# FinalDesignCurrentMirror.net
KiCad netlist of a schematic drawn in Altium Designer
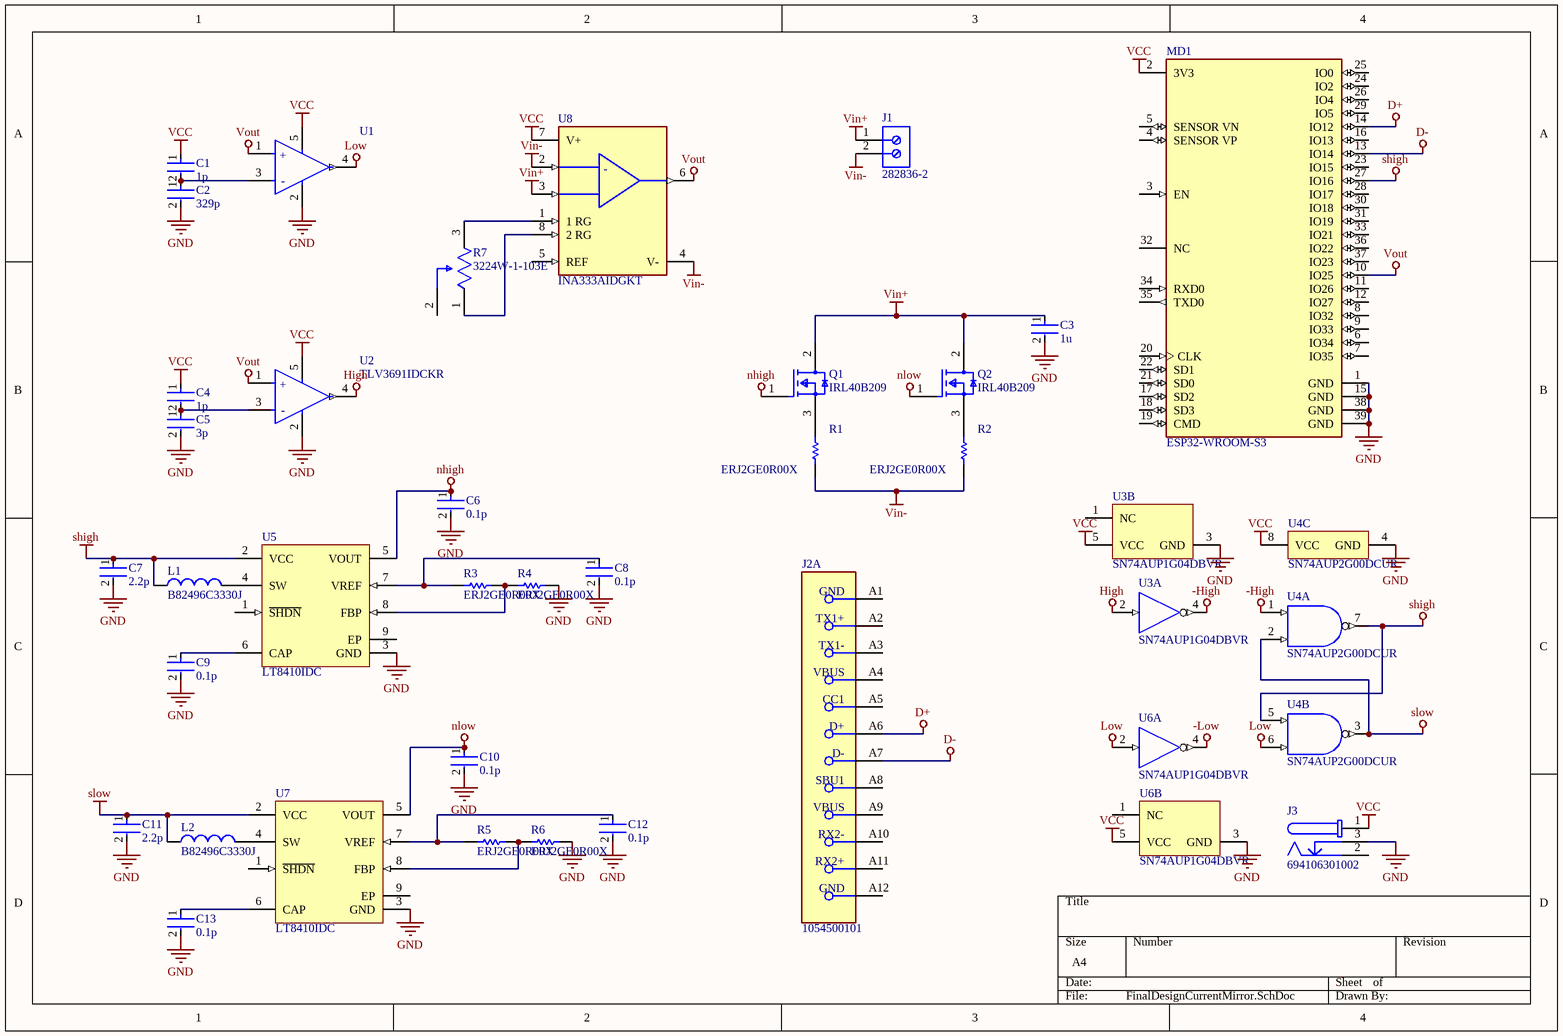
[diagram p0: FinalDesignCurrentMirror.SchDoc]

(export (version "E")
  (design (tool "Eeschema 10.0.6"))
  (components
    (comp (ref "C1")
      (value "1p")
      (footprint "FP-GRM188-0_1-e0_2_0_55-IPC_A")
      (description "Chip Multilayer Ceramic Capacitors for General Purpose, 0603, 10uF, X5R, 15%, 20%, 6.3V")
      (fields (field (name "VOLTAGE") "6.3V") (field (name "TOLERANCE") "20%"))
      (libsource (lib "Altium Content Vault") (part "02cd4be3c70576c341d710602a673aa"))
    )
    (comp (ref "C2")
      (value "329p")
      (footprint "FP-GRM188-0_1-e0_2_0_55-IPC_A")
      (description "Chip Multilayer Ceramic Capacitors for General Purpose, 0603, 10uF, X5R, 15%, 20%, 6.3V")
      (fields (field (name "VOLTAGE") "6.3V") (field (name "TOLERANCE") "20%"))
      (libsource (lib "Altium Content Vault") (part "02cd4be3c70576c341d710602a673aa"))
    )
    (comp (ref "C3")
      (value "1u")
      (footprint "FP-GRM188-0_1-e0_2_0_55-IPC_A")
      (description "Chip Multilayer Ceramic Capacitors for General Purpose, 0603, 10uF, X5R, 15%, 20%, 6.3V")
      (fields (field (name "VOLTAGE") "6.3V") (field (name "TOLERANCE") "20%"))
      (libsource (lib "Altium Content Vault") (part "02cd4be3c70576c341d710602a673aa"))
    )
    (comp (ref "C4")
      (value "1p")
      (footprint "FP-GRM188-0_1-e0_2_0_55-IPC_A")
      (description "Chip Multilayer Ceramic Capacitors for General Purpose, 0603, 10uF, X5R, 15%, 20%, 6.3V")
      (fields (field (name "VOLTAGE") "6.3V") (field (name "TOLERANCE") "20%"))
      (libsource (lib "Altium Content Vault") (part "02cd4be3c70576c341d710602a673aa"))
    )
    (comp (ref "C5")
      (value "3p")
      (footprint "FP-GRM188-0_1-e0_2_0_55-IPC_A")
      (description "Chip Multilayer Ceramic Capacitors for General Purpose, 0603, 10uF, X5R, 15%, 20%, 6.3V")
      (fields (field (name "VOLTAGE") "6.3V") (field (name "TOLERANCE") "20%"))
      (libsource (lib "Altium Content Vault") (part "02cd4be3c70576c341d710602a673aa"))
    )
    (comp (ref "C6")
      (value "0.1p")
      (footprint "FP-GRM188-0_1-e0_2_0_55-IPC_A")
      (description "Chip Multilayer Ceramic Capacitors for General Purpose, 0603, 10uF, X5R, 15%, 20%, 6.3V")
      (fields (field (name "VOLTAGE") "6.3V") (field (name "TOLERANCE") "20%"))
      (libsource (lib "Altium Content Vault") (part "02cd4be3c70576c341d710602a673aa"))
    )
    (comp (ref "C7")
      (value "2.2p")
      (footprint "FP-GRM188-0_1-e0_2_0_55-IPC_A")
      (description "Chip Multilayer Ceramic Capacitors for General Purpose, 0603, 10uF, X5R, 15%, 20%, 6.3V")
      (fields (field (name "VOLTAGE") "6.3V") (field (name "TOLERANCE") "20%"))
      (libsource (lib "Altium Content Vault") (part "02cd4be3c70576c341d710602a673aa"))
    )
    (comp (ref "C8")
      (value "0.1p")
      (footprint "FP-GRM188-0_1-e0_2_0_55-IPC_A")
      (description "Chip Multilayer Ceramic Capacitors for General Purpose, 0603, 10uF, X5R, 15%, 20%, 6.3V")
      (fields (field (name "VOLTAGE") "6.3V") (field (name "TOLERANCE") "20%"))
      (libsource (lib "Altium Content Vault") (part "02cd4be3c70576c341d710602a673aa"))
    )
    (comp (ref "C9")
      (value "0.1p")
      (footprint "FP-GRM188-0_1-e0_2_0_55-IPC_A")
      (description "Chip Multilayer Ceramic Capacitors for General Purpose, 0603, 10uF, X5R, 15%, 20%, 6.3V")
      (fields (field (name "VOLTAGE") "6.3V") (field (name "TOLERANCE") "20%"))
      (libsource (lib "Altium Content Vault") (part "02cd4be3c70576c341d710602a673aa"))
    )
    (comp (ref "C10")
      (value "0.1p")
      (footprint "FP-GRM188-0_1-e0_2_0_55-IPC_A")
      (description "Chip Multilayer Ceramic Capacitors for General Purpose, 0603, 10uF, X5R, 15%, 20%, 6.3V")
      (fields (field (name "VOLTAGE") "6.3V") (field (name "TOLERANCE") "20%"))
      (libsource (lib "Altium Content Vault") (part "02cd4be3c70576c341d710602a673aa"))
    )
    (comp (ref "C11")
      (value "2.2p")
      (footprint "FP-GRM188-0_1-e0_2_0_55-IPC_A")
      (description "Chip Multilayer Ceramic Capacitors for General Purpose, 0603, 10uF, X5R, 15%, 20%, 6.3V")
      (fields (field (name "VOLTAGE") "6.3V") (field (name "TOLERANCE") "20%"))
      (libsource (lib "Altium Content Vault") (part "02cd4be3c70576c341d710602a673aa"))
    )
    (comp (ref "C12")
      (value "0.1p")
      (footprint "FP-GRM188-0_1-e0_2_0_55-IPC_A")
      (description "Chip Multilayer Ceramic Capacitors for General Purpose, 0603, 10uF, X5R, 15%, 20%, 6.3V")
      (fields (field (name "VOLTAGE") "6.3V") (field (name "TOLERANCE") "20%"))
      (libsource (lib "Altium Content Vault") (part "02cd4be3c70576c341d710602a673aa"))
    )
    (comp (ref "C13")
      (value "0.1p")
      (footprint "FP-GRM188-0_1-e0_2_0_55-IPC_A")
      (description "Chip Multilayer Ceramic Capacitors for General Purpose, 0603, 10uF, X5R, 15%, 20%, 6.3V")
      (fields (field (name "VOLTAGE") "6.3V") (field (name "TOLERANCE") "20%"))
      (libsource (lib "Altium Content Vault") (part "02cd4be3c70576c341d710602a673aa"))
    )
    (comp (ref "J1")
      (value "282836-2")
      (footprint "TECO-282836-2_V")
      (description "Female Header, Pitch 5 mm, 1 x 2 Position, Height 10 mm, Tail Length 3.5 mm, Rohs, Bulk")
      (fields (field (name "VOLTAGE") "300V") (field (name "MANUFACTURER") "TE Connectivity"))
      (libsource (lib "Altium Content Vault") (part "CN-1P-F-TB2"))
    )
    (comp (ref "J2")
      (value "1054500101")
      (footprint "FP-1054500101-MFG")
      (description "USB Shielded I/O Receptacle; Type C; Right Angle; Surface Mount; Gold over Nickel")
      (fields (field (name "MANUFACTURER") "Molex"))
      (libsource (lib "Altium Content Vault") (part "9808b19ecaf079fb99eed69f0495cd0"))
    )
    (comp (ref "J3")
      (value "694106301002")
      (footprint "694106301002")
      (libsource (lib "Altium Content Vault") (part "DC Power Jack"))
    )
    (comp (ref "L1")
      (value "B82496C3330J")
      (footprint "INDC1608X90X30LL10T20")
      (fields (field (name "MANUFACTURER") "EPCOS-(TDK)") (field (name "TOLERANCE") "±5%"))
      (libsource (lib "Altium Content Vault") (part "IND-2"))
    )
    (comp (ref "L2")
      (value "B82496C3330J")
      (footprint "INDC1608X90X30LL10T20")
      (fields (field (name "MANUFACTURER") "EPCOS-(TDK)") (field (name "TOLERANCE") "±5%"))
      (libsource (lib "Altium Content Vault") (part "IND-2"))
    )
    (comp (ref "MD1")
      (value "ESP32-WROOM-S3")
      (footprint "FP-ESP32-WROOM-32D-MFG")
      (description "WIFI MODULE 32MBITS SPI FLASH")
      (fields
        (field (name "OCTOPART") "https://octopart.com/esp32-wroom-32d-espressif+systems-91040050")
        (field (name "MANUFACTURER") "Espressif Systems")
      )
      (libsource (lib "Altium Content Vault") (part "a031a76f8c27026a7a7f4657ff233a3"))
    )
    (comp (ref "Q1")
      (value "IRL40B209")
      (footprint "FP-PG-TO220-3-MFG")
      (description "MOSFET N-CH 40V 195A")
      (libsource (lib "Altium Content Vault") (part "277670f45256a45703965f138927d09"))
    )
    (comp (ref "Q2")
      (value "IRL40B209")
      (footprint "FP-PG-TO220-3-MFG")
      (description "MOSFET N-CH 40V 195A")
      (libsource (lib "Altium Content Vault") (part "277670f45256a45703965f138927d09"))
    )
    (comp (ref "R1")
      (value "ERJ2GE0R00X")
      (footprint "RESC1005X40X25LL05T05")
      (description "Chip Resistor, 0 Ohm, 0.1 W, -55 to 155 degC, 0402 (1005 Metric), RoHS, Tape and Reel")
      (fields (field (name "MANUFACTURER") "Panasonic") (field (name "TOLERANCE") "5%"))
      (libsource (lib "Altium Content Vault") (part "RES-2"))
    )
    (comp (ref "R2")
      (value "ERJ2GE0R00X")
      (footprint "RESC1005X40X25LL05T05")
      (description "Chip Resistor, 0 Ohm, 0.1 W, -55 to 155 degC, 0402 (1005 Metric), RoHS, Tape and Reel")
      (fields (field (name "MANUFACTURER") "Panasonic") (field (name "TOLERANCE") "5%"))
      (libsource (lib "Altium Content Vault") (part "RES-2"))
    )
    (comp (ref "R3")
      (value "ERJ2GE0R00X")
      (footprint "RESC1005X40X25LL05T05")
      (description "Chip Resistor, 0 Ohm, 0.1 W, -55 to 155 degC, 0402 (1005 Metric), RoHS, Tape and Reel")
      (fields (field (name "MANUFACTURER") "Panasonic") (field (name "TOLERANCE") "5%"))
      (libsource (lib "Altium Content Vault") (part "RES-2"))
    )
    (comp (ref "R4")
      (value "ERJ2GE0R00X")
      (footprint "RESC1005X40X25LL05T05")
      (description "Chip Resistor, 0 Ohm, 0.1 W, -55 to 155 degC, 0402 (1005 Metric), RoHS, Tape and Reel")
      (fields (field (name "MANUFACTURER") "Panasonic") (field (name "TOLERANCE") "5%"))
      (libsource (lib "Altium Content Vault") (part "RES-2"))
    )
    (comp (ref "R5")
      (value "ERJ2GE0R00X")
      (footprint "RESC1005X40X25LL05T05")
      (description "Chip Resistor, 0 Ohm, 0.1 W, -55 to 155 degC, 0402 (1005 Metric), RoHS, Tape and Reel")
      (fields (field (name "MANUFACTURER") "Panasonic") (field (name "TOLERANCE") "5%"))
      (libsource (lib "Altium Content Vault") (part "RES-2"))
    )
    (comp (ref "R6")
      (value "ERJ2GE0R00X")
      (footprint "RESC1005X40X25LL05T05")
      (description "Chip Resistor, 0 Ohm, 0.1 W, -55 to 155 degC, 0402 (1005 Metric), RoHS, Tape and Reel")
      (fields (field (name "MANUFACTURER") "Panasonic") (field (name "TOLERANCE") "5%"))
      (libsource (lib "Altium Content Vault") (part "RES-2"))
    )
    (comp (ref "R7")
      (value "3224W-1-103E")
      (footprint "FP-3224W-MFG")
      (description "TRIMMER 10K OHM 0.25W J LEAD TOP")
      (fields (field (name "TOLERANCE") "10%") (field (name "MANUFACTURER") "Bourns"))
      (libsource (lib "Altium Content Vault") (part "83d3d349ed884d1db45cec512f27eb6"))
    )
    (comp (ref "U1")
      (value "~")
      (footprint "FP-DCK0005A-IPC_A")
      (description "IC COMPARATOR NANO-POWER SC70-5")
      (libsource (lib "Altium Content Vault") (part "3dae5d43319efa9f60be5f7de20330d"))
    )
    (comp (ref "U2")
      (value "TLV3691IDCKR")
      (footprint "FP-DCK0005A-IPC_A")
      (description "IC COMPARATOR NANO-POWER SC70-5")
      (libsource (lib "Altium Content Vault") (part "3dae5d43319efa9f60be5f7de20330d"))
    )
    (comp (ref "U3")
      (value "SN74AUP1G04DBVR")
      (footprint "DBV0005A_L")
      (description "Low-Power Single Inverter Gate, DBV0005A, LARGE T&R")
      (fields
        (field (name "GENERIC PART NUMBER") "SN74AUP1G04")
        (field (name "MANUFACTURER") "Texas Instruments")
      )
      (libsource (lib "Altium Content Vault") (part "TI-SN74XXX1XX4-XX-5"))
    )
    (comp (ref "U4")
      (value "SN74AUP2G00DCUR")
      (footprint "DCU0008A_L")
      (description "Low-Power Dual 2-Input Positive-NAND Gate, DCU0008A, LARGE T&R")
      (fields
        (field (name "GENERIC PART NUMBER") "SN74AUP2G00")
        (field (name "MANUFACTURER") "Texas Instruments")
      )
      (libsource (lib "Altium Content Vault") (part "TI-SN74XXX2GXXX-8"))
    )
    (comp (ref "U5")
      (value "LT8410IDC")
      (footprint "LT-DC8_V")
      (fields
        (field (name "PARTNUMBER") "LT8410IDC-1#TRMPBF")
        (field (name "MANUFACTURER") "Linear Technology")
      )
      (libsource (lib "Altium Content Vault") (part "LT-LT8410-1_8410-DC8-8"))
    )
    (comp (ref "U6")
      (value "SN74AUP1G04DBVR")
      (footprint "DBV0005A_L")
      (description "Low-Power Single Inverter Gate, DBV0005A, LARGE T&R")
      (fields
        (field (name "GENERIC PART NUMBER") "SN74AUP1G04")
        (field (name "MANUFACTURER") "Texas Instruments")
      )
      (libsource (lib "Altium Content Vault") (part "TI-SN74XXX1XX4-XX-5"))
    )
    (comp (ref "U7")
      (value "LT8410IDC")
      (footprint "LT-DC8_V")
      (fields
        (field (name "PARTNUMBER") "LT8410IDC-1#TRMPBF")
        (field (name "MANUFACTURER") "Linear Technology")
      )
      (libsource (lib "Altium Content Vault") (part "LT-LT8410-1_8410-DC8-8"))
    )
    (comp (ref "U8")
      (value "INA333AIDGKT")
      (footprint "FP-DGK0008A-MFG")
      (description "Instrumentation Amplifier 1 Circuit Rail-to-Rail 8-VSSOP")
      (fields (field (name "MANUFACTURER") "Texas Instruments"))
      (libsource (lib "Altium Content Vault") (part "14c63953c288e0173d78c5cf827a12c"))
    )
  )
  (nets
    (net (code "1") (name "-High") (class "Default")
      (node (ref "U3") (pin "4") (pinfunction "Y_4") (pintype "output"))
      (node (ref "U4") (pin "1") (pinfunction "1A_1") (pintype "input"))
    )
    (net (code "2") (name "-Low") (class "Default")
      (node (ref "U6") (pin "4") (pinfunction "Y_4") (pintype "output"))
    )
    (net (code "3") (name "D+") (class "Default")
      (node (ref "J2") (pin "A6") (pinfunction "D+_A6") (pintype "passive"))
      (node (ref "MD1") (pin "14") (pinfunction "IO12_14") (pintype "bidirectional"))
    )
    (net (code "4") (name "D-") (class "Default")
      (node (ref "J2") (pin "A7") (pinfunction "D-_A7") (pintype "passive"))
      (node (ref "MD1") (pin "13") (pinfunction "IO14_13") (pintype "bidirectional"))
    )
    (net (code "5") (name "GND") (class "Default")
      (node (ref "C10") (pin "2") (pinfunction "2_2") (pintype "passive"))
      (node (ref "C11") (pin "2") (pinfunction "2_2") (pintype "passive"))
      (node (ref "C12") (pin "2") (pinfunction "2_2") (pintype "passive"))
      (node (ref "C13") (pin "2") (pinfunction "2_2") (pintype "passive"))
      (node (ref "C2") (pin "2") (pinfunction "2_2") (pintype "passive"))
      (node (ref "C3") (pin "2") (pinfunction "2_2") (pintype "passive"))
      (node (ref "C5") (pin "2") (pinfunction "2_2") (pintype "passive"))
      (node (ref "C6") (pin "2") (pinfunction "2_2") (pintype "passive"))
      (node (ref "C7") (pin "2") (pinfunction "2_2") (pintype "passive"))
      (node (ref "C8") (pin "2") (pinfunction "2_2") (pintype "passive"))
      (node (ref "C9") (pin "2") (pinfunction "2_2") (pintype "passive"))
      (node (ref "J3") (pin "3") (pinfunction "3_3") (pintype "passive"))
      (node (ref "MD1") (pin "1") (pinfunction "GND_1") (pintype "power_in"))
      (node (ref "MD1") (pin "15") (pinfunction "GND_15") (pintype "power_in"))
      (node (ref "MD1") (pin "38") (pinfunction "GND_38") (pintype "power_in"))
      (node (ref "MD1") (pin "39") (pinfunction "GND_39") (pintype "power_in"))
      (node (ref "R4") (pin "1") (pinfunction "1_1") (pintype "passive"))
      (node (ref "R6") (pin "1") (pinfunction "1_1") (pintype "passive"))
      (node (ref "U1") (pin "2") (pinfunction "GND_2") (pintype "power_in"))
      (node (ref "U2") (pin "2") (pinfunction "GND_2") (pintype "power_in"))
      (node (ref "U3") (pin "3") (pinfunction "GND_3") (pintype "power_in"))
      (node (ref "U4") (pin "4") (pinfunction "GND_4") (pintype "power_in"))
      (node (ref "U5") (pin "3") (pinfunction "GND_3") (pintype "power_in"))
      (node (ref "U6") (pin "3") (pinfunction "GND_3") (pintype "power_in"))
      (node (ref "U7") (pin "3") (pinfunction "GND_3") (pintype "power_in"))
    )
    (net (code "6") (name "High") (class "Default")
      (node (ref "U2") (pin "4") (pinfunction "OUT_4") (pintype "output"))
      (node (ref "U3") (pin "2") (pinfunction "A_2") (pintype "input"))
    )
    (net (code "7") (name "Low") (class "Default")
      (node (ref "U1") (pin "4") (pinfunction "OUT_4") (pintype "output"))
      (node (ref "U4") (pin "6") (pinfunction "2B_6") (pintype "input"))
      (node (ref "U6") (pin "2") (pinfunction "A_2") (pintype "input"))
    )
    (net (code "8") (name "Net-(Q1-S)") (class "Default")
      (node (ref "Q1") (pin "3") (pinfunction "S_3") (pintype "passive"))
      (node (ref "R1") (pin "2") (pinfunction "2_2") (pintype "passive"))
    )
    (net (code "9") (name "Net-(Q2-S)") (class "Default")
      (node (ref "Q2") (pin "3") (pinfunction "S_3") (pintype "passive"))
      (node (ref "R2") (pin "2") (pinfunction "2_2") (pintype "passive"))
    )
    (net (code "10") (name "Net-(R7-CCW)") (class "Default")
      (node (ref "R7") (pin "1") (pinfunction "CCW_1") (pintype "passive"))
      (node (ref "U8") (pin "8") (pinfunction "2_RG_8") (pintype "input"))
    )
    (net (code "11") (name "Net-(R7-CW)") (class "Default")
      (node (ref "R7") (pin "3") (pinfunction "CW_3") (pintype "passive"))
      (node (ref "U8") (pin "1") (pinfunction "1_RG_1") (pintype "input"))
    )
    (net (code "12") (name "Net-(U1-IN-)") (class "Default")
      (node (ref "C1") (pin "2") (pinfunction "2_2") (pintype "passive"))
      (node (ref "C2") (pin "1") (pinfunction "1_1") (pintype "passive"))
      (node (ref "U1") (pin "3") (pinfunction "IN-_3") (pintype "tri_state"))
    )
    (net (code "13") (name "Net-(U2-IN-)") (class "Default")
      (node (ref "C4") (pin "2") (pinfunction "2_2") (pintype "passive"))
      (node (ref "C5") (pin "1") (pinfunction "1_1") (pintype "passive"))
      (node (ref "U2") (pin "3") (pinfunction "IN-_3") (pintype "tri_state"))
    )
    (net (code "14") (name "Net-(U5-CAP)") (class "Default")
      (node (ref "C9") (pin "1") (pinfunction "1_1") (pintype "passive"))
      (node (ref "U5") (pin "6") (pinfunction "CAP_6") (pintype "passive"))
    )
    (net (code "15") (name "Net-(U5-FBP)") (class "Default")
      (node (ref "R3") (pin "1") (pinfunction "1_1") (pintype "passive"))
      (node (ref "R4") (pin "2") (pinfunction "2_2") (pintype "passive"))
      (node (ref "U5") (pin "8") (pinfunction "FBP_8") (pintype "input"))
    )
    (net (code "16") (name "Net-(U5-SW)") (class "Default")
      (node (ref "L1") (pin "2") (pinfunction "2_2") (pintype "passive"))
      (node (ref "U5") (pin "4") (pinfunction "SW_4") (pintype "passive"))
    )
    (net (code "17") (name "Net-(U5-VREF)") (class "Default")
      (node (ref "C8") (pin "1") (pinfunction "1_1") (pintype "passive"))
      (node (ref "R3") (pin "2") (pinfunction "2_2") (pintype "passive"))
      (node (ref "U5") (pin "7") (pinfunction "VREF_7") (pintype "input"))
    )
    (net (code "18") (name "Net-(U7-CAP)") (class "Default")
      (node (ref "C13") (pin "1") (pinfunction "1_1") (pintype "passive"))
      (node (ref "U7") (pin "6") (pinfunction "CAP_6") (pintype "passive"))
    )
    (net (code "19") (name "Net-(U7-FBP)") (class "Default")
      (node (ref "R5") (pin "1") (pinfunction "1_1") (pintype "passive"))
      (node (ref "R6") (pin "2") (pinfunction "2_2") (pintype "passive"))
      (node (ref "U7") (pin "8") (pinfunction "FBP_8") (pintype "input"))
    )
    (net (code "20") (name "Net-(U7-SW)") (class "Default")
      (node (ref "L2") (pin "2") (pinfunction "2_2") (pintype "passive"))
      (node (ref "U7") (pin "4") (pinfunction "SW_4") (pintype "passive"))
    )
    (net (code "21") (name "Net-(U7-VREF)") (class "Default")
      (node (ref "C12") (pin "1") (pinfunction "1_1") (pintype "passive"))
      (node (ref "R5") (pin "2") (pinfunction "2_2") (pintype "passive"))
      (node (ref "U7") (pin "7") (pinfunction "VREF_7") (pintype "input"))
    )
    (net (code "22") (name "VCC") (class "Default")
      (node (ref "C1") (pin "1") (pinfunction "1_1") (pintype "passive"))
      (node (ref "C4") (pin "1") (pinfunction "1_1") (pintype "passive"))
      (node (ref "J3") (pin "1") (pinfunction "1_1") (pintype "passive"))
      (node (ref "MD1") (pin "2") (pinfunction "3V3_2") (pintype "power_in"))
      (node (ref "U1") (pin "5") (pinfunction "VCC_5") (pintype "power_in"))
      (node (ref "U2") (pin "5") (pinfunction "VCC_5") (pintype "power_in"))
      (node (ref "U3") (pin "5") (pinfunction "VCC_5") (pintype "power_in"))
      (node (ref "U4") (pin "8") (pinfunction "VCC_8") (pintype "power_in"))
      (node (ref "U6") (pin "5") (pinfunction "VCC_5") (pintype "power_in"))
      (node (ref "U8") (pin "7") (pinfunction "V+_7") (pintype "power_in"))
    )
    (net (code "23") (name "Vin+") (class "Default")
      (node (ref "C3") (pin "1") (pinfunction "1_1") (pintype "passive"))
      (node (ref "J1") (pin "1") (pinfunction "1_1") (pintype "passive"))
      (node (ref "Q1") (pin "2") (pinfunction "D_2") (pintype "passive"))
      (node (ref "Q2") (pin "2") (pinfunction "D_2") (pintype "passive"))
      (node (ref "U8") (pin "3") (pinfunction "VIN+_3") (pintype "input"))
    )
    (net (code "24") (name "Vin-") (class "Default")
      (node (ref "J1") (pin "2") (pinfunction "2_2") (pintype "passive"))
      (node (ref "R1") (pin "1") (pinfunction "1_1") (pintype "passive"))
      (node (ref "R2") (pin "1") (pinfunction "1_1") (pintype "passive"))
      (node (ref "U8") (pin "2") (pinfunction "VIN-_2") (pintype "input"))
      (node (ref "U8") (pin "4") (pinfunction "V-_4") (pintype "power_in"))
    )
    (net (code "25") (name "Vout") (class "Default")
      (node (ref "MD1") (pin "10") (pinfunction "IO25_10") (pintype "bidirectional"))
      (node (ref "U1") (pin "1") (pinfunction "IN+_1") (pintype "tri_state"))
      (node (ref "U2") (pin "1") (pinfunction "IN+_1") (pintype "tri_state"))
      (node (ref "U8") (pin "6") (pinfunction "VOUT_6") (pintype "output"))
    )
    (net (code "26") (name "nhigh") (class "Default")
      (node (ref "C6") (pin "1") (pinfunction "1_1") (pintype "passive"))
      (node (ref "Q1") (pin "1") (pinfunction "G_1") (pintype "passive"))
      (node (ref "U5") (pin "5") (pinfunction "VOUT_5") (pintype "power_in"))
    )
    (net (code "27") (name "nlow") (class "Default")
      (node (ref "C10") (pin "1") (pinfunction "1_1") (pintype "passive"))
      (node (ref "Q2") (pin "1") (pinfunction "G_1") (pintype "passive"))
      (node (ref "U7") (pin "5") (pinfunction "VOUT_5") (pintype "power_in"))
    )
    (net (code "28") (name "shigh") (class "Default")
      (node (ref "C7") (pin "1") (pinfunction "1_1") (pintype "passive"))
      (node (ref "L1") (pin "1") (pinfunction "1_1") (pintype "passive"))
      (node (ref "MD1") (pin "27") (pinfunction "IO16_27") (pintype "bidirectional"))
      (node (ref "U4") (pin "5") (pinfunction "2A_5") (pintype "input"))
      (node (ref "U4") (pin "7") (pinfunction "1Y_7") (pintype "output"))
      (node (ref "U5") (pin "2") (pinfunction "VCC_2") (pintype "power_in"))
    )
    (net (code "29") (name "slow") (class "Default")
      (node (ref "C11") (pin "1") (pinfunction "1_1") (pintype "passive"))
      (node (ref "L2") (pin "1") (pinfunction "1_1") (pintype "passive"))
      (node (ref "U4") (pin "2") (pinfunction "1B_2") (pintype "input"))
      (node (ref "U4") (pin "3") (pinfunction "2Y_3") (pintype "output"))
      (node (ref "U7") (pin "2") (pinfunction "VCC_2") (pintype "power_in"))
    )
    (net (code "30") (name "unconnected-(J2A-CC1-PadA5)") (class "Default")
      (node (ref "J2") (pin "A5") (pinfunction "CC1_A5") (pintype "passive"))
    )
    (net (code "31") (name "unconnected-(J2A-GND-PadA1)") (class "Default")
      (node (ref "J2") (pin "A1") (pinfunction "GND_A1") (pintype "passive"))
    )
    (net (code "32") (name "unconnected-(J2A-GND-PadA12)") (class "Default")
      (node (ref "J2") (pin "A12") (pinfunction "GND_A12") (pintype "passive"))
    )
    (net (code "33") (name "unconnected-(J2A-RX2+-PadA11)") (class "Default")
      (node (ref "J2") (pin "A11") (pinfunction "RX2+_A11") (pintype "passive"))
    )
    (net (code "34") (name "unconnected-(J2A-RX2--PadA10)") (class "Default")
      (node (ref "J2") (pin "A10") (pinfunction "RX2-_A10") (pintype "passive"))
    )
    (net (code "35") (name "unconnected-(J2A-SBU1-PadA8)") (class "Default")
      (node (ref "J2") (pin "A8") (pinfunction "SBU1_A8") (pintype "passive"))
    )
    (net (code "36") (name "unconnected-(J2A-TX1+-PadA2)") (class "Default")
      (node (ref "J2") (pin "A2") (pinfunction "TX1+_A2") (pintype "passive"))
    )
    (net (code "37") (name "unconnected-(J2A-TX1--PadA3)") (class "Default")
      (node (ref "J2") (pin "A3") (pinfunction "TX1-_A3") (pintype "passive"))
    )
    (net (code "38") (name "unconnected-(J2A-VBUS-PadA4)") (class "Default")
      (node (ref "J2") (pin "A4") (pinfunction "VBUS_A4") (pintype "passive"))
    )
    (net (code "39") (name "unconnected-(J2A-VBUS-PadA9)") (class "Default")
      (node (ref "J2") (pin "A9") (pinfunction "VBUS_A9") (pintype "passive"))
    )
    (net (code "40") (name "unconnected-(J3-Pad2)") (class "Default")
      (node (ref "J3") (pin "2") (pinfunction "2_2") (pintype "passive"))
    )
    (net (code "41") (name "unconnected-(MD1-CLK-Pad20)") (class "Default")
      (node (ref "MD1") (pin "20") (pinfunction "CLK_20") (pintype "input"))
    )
    (net (code "42") (name "unconnected-(MD1-CMD-Pad19)") (class "Default")
      (node (ref "MD1") (pin "19") (pinfunction "CMD_19") (pintype "bidirectional"))
    )
    (net (code "43") (name "unconnected-(MD1-EN-Pad3)") (class "Default")
      (node (ref "MD1") (pin "3") (pinfunction "EN_3") (pintype "input"))
    )
    (net (code "44") (name "unconnected-(MD1-IO0-Pad25)") (class "Default")
      (node (ref "MD1") (pin "25") (pinfunction "IO0_25") (pintype "bidirectional"))
    )
    (net (code "45") (name "unconnected-(MD1-IO2-Pad24)") (class "Default")
      (node (ref "MD1") (pin "24") (pinfunction "IO2_24") (pintype "bidirectional"))
    )
    (net (code "46") (name "unconnected-(MD1-IO4-Pad26)") (class "Default")
      (node (ref "MD1") (pin "26") (pinfunction "IO4_26") (pintype "bidirectional"))
    )
    (net (code "47") (name "unconnected-(MD1-IO5-Pad29)") (class "Default")
      (node (ref "MD1") (pin "29") (pinfunction "IO5_29") (pintype "bidirectional"))
    )
    (net (code "48") (name "unconnected-(MD1-IO13-Pad16)") (class "Default")
      (node (ref "MD1") (pin "16") (pinfunction "IO13_16") (pintype "bidirectional"))
    )
    (net (code "49") (name "unconnected-(MD1-IO15-Pad23)") (class "Default")
      (node (ref "MD1") (pin "23") (pinfunction "IO15_23") (pintype "bidirectional"))
    )
    (net (code "50") (name "unconnected-(MD1-IO17-Pad28)") (class "Default")
      (node (ref "MD1") (pin "28") (pinfunction "IO17_28") (pintype "bidirectional"))
    )
    (net (code "51") (name "unconnected-(MD1-IO18-Pad30)") (class "Default")
      (node (ref "MD1") (pin "30") (pinfunction "IO18_30") (pintype "bidirectional"))
    )
    (net (code "52") (name "unconnected-(MD1-IO19-Pad31)") (class "Default")
      (node (ref "MD1") (pin "31") (pinfunction "IO19_31") (pintype "bidirectional"))
    )
    (net (code "53") (name "unconnected-(MD1-IO21-Pad33)") (class "Default")
      (node (ref "MD1") (pin "33") (pinfunction "IO21_33") (pintype "bidirectional"))
    )
    (net (code "54") (name "unconnected-(MD1-IO22-Pad36)") (class "Default")
      (node (ref "MD1") (pin "36") (pinfunction "IO22_36") (pintype "bidirectional"))
    )
    (net (code "55") (name "unconnected-(MD1-IO23-Pad37)") (class "Default")
      (node (ref "MD1") (pin "37") (pinfunction "IO23_37") (pintype "bidirectional"))
    )
    (net (code "56") (name "unconnected-(MD1-IO26-Pad11)") (class "Default")
      (node (ref "MD1") (pin "11") (pinfunction "IO26_11") (pintype "bidirectional"))
    )
    (net (code "57") (name "unconnected-(MD1-IO27-Pad12)") (class "Default")
      (node (ref "MD1") (pin "12") (pinfunction "IO27_12") (pintype "bidirectional"))
    )
    (net (code "58") (name "unconnected-(MD1-IO32-Pad8)") (class "Default")
      (node (ref "MD1") (pin "8") (pinfunction "IO32_8") (pintype "bidirectional"))
    )
    (net (code "59") (name "unconnected-(MD1-IO33-Pad9)") (class "Default")
      (node (ref "MD1") (pin "9") (pinfunction "IO33_9") (pintype "bidirectional"))
    )
    (net (code "60") (name "unconnected-(MD1-IO34-Pad6)") (class "Default")
      (node (ref "MD1") (pin "6") (pinfunction "IO34_6") (pintype "bidirectional"))
    )
    (net (code "61") (name "unconnected-(MD1-IO35-Pad7)") (class "Default")
      (node (ref "MD1") (pin "7") (pinfunction "IO35_7") (pintype "bidirectional"))
    )
    (net (code "62") (name "unconnected-(MD1-NC-Pad32)") (class "Default")
      (node (ref "MD1") (pin "32") (pinfunction "NC_32") (pintype "passive"))
    )
    (net (code "63") (name "unconnected-(MD1-RXD0-Pad34)") (class "Default")
      (node (ref "MD1") (pin "34") (pinfunction "RXD0_34") (pintype "input"))
    )
    (net (code "64") (name "unconnected-(MD1-SD0-Pad21)") (class "Default")
      (node (ref "MD1") (pin "21") (pinfunction "SD0_21") (pintype "bidirectional"))
    )
    (net (code "65") (name "unconnected-(MD1-SD1-Pad22)") (class "Default")
      (node (ref "MD1") (pin "22") (pinfunction "SD1_22") (pintype "bidirectional"))
    )
    (net (code "66") (name "unconnected-(MD1-SD2-Pad17)") (class "Default")
      (node (ref "MD1") (pin "17") (pinfunction "SD2_17") (pintype "bidirectional"))
    )
    (net (code "67") (name "unconnected-(MD1-SD3-Pad18)") (class "Default")
      (node (ref "MD1") (pin "18") (pinfunction "SD3_18") (pintype "bidirectional"))
    )
    (net (code "68") (name "unconnected-(MD1-SENSOR_VN-Pad5)") (class "Default")
      (node (ref "MD1") (pin "5") (pinfunction "SENSOR_VN_5") (pintype "bidirectional"))
    )
    (net (code "69") (name "unconnected-(MD1-SENSOR_VP-Pad4)") (class "Default")
      (node (ref "MD1") (pin "4") (pinfunction "SENSOR_VP_4") (pintype "bidirectional"))
    )
    (net (code "70") (name "unconnected-(MD1-TXD0-Pad35)") (class "Default")
      (node (ref "MD1") (pin "35") (pinfunction "TXD0_35") (pintype "output"))
    )
    (net (code "71") (name "unconnected-(R7-WIPER-Pad2)") (class "Default")
      (node (ref "R7") (pin "2") (pinfunction "WIPER_2") (pintype "passive"))
    )
    (net (code "72") (name "unconnected-(U3B-NC-Pad1)") (class "Default")
      (node (ref "U3") (pin "1") (pinfunction "NC_1") (pintype "passive"))
    )
    (net (code "73") (name "unconnected-(U5-EP-Pad9)") (class "Default")
      (node (ref "U5") (pin "9") (pinfunction "EP_9") (pintype "power_in"))
    )
    (net (code "74") (name "unconnected-(U5-~{SHDN}-Pad1)") (class "Default")
      (node (ref "U5") (pin "1") (pinfunction "~{SHDN}_1") (pintype "input"))
    )
    (net (code "75") (name "unconnected-(U6B-NC-Pad1)") (class "Default")
      (node (ref "U6") (pin "1") (pinfunction "NC_1") (pintype "passive"))
    )
    (net (code "76") (name "unconnected-(U7-EP-Pad9)") (class "Default")
      (node (ref "U7") (pin "9") (pinfunction "EP_9") (pintype "power_in"))
    )
    (net (code "77") (name "unconnected-(U7-~{SHDN}-Pad1)") (class "Default")
      (node (ref "U7") (pin "1") (pinfunction "~{SHDN}_1") (pintype "input"))
    )
    (net (code "78") (name "unconnected-(U8-REF-Pad5)") (class "Default")
      (node (ref "U8") (pin "5") (pinfunction "REF_5") (pintype "input"))
    )
  )
)
